# ETHERUNO.net
KiCad netlist of a schematic drawn in EAGLE
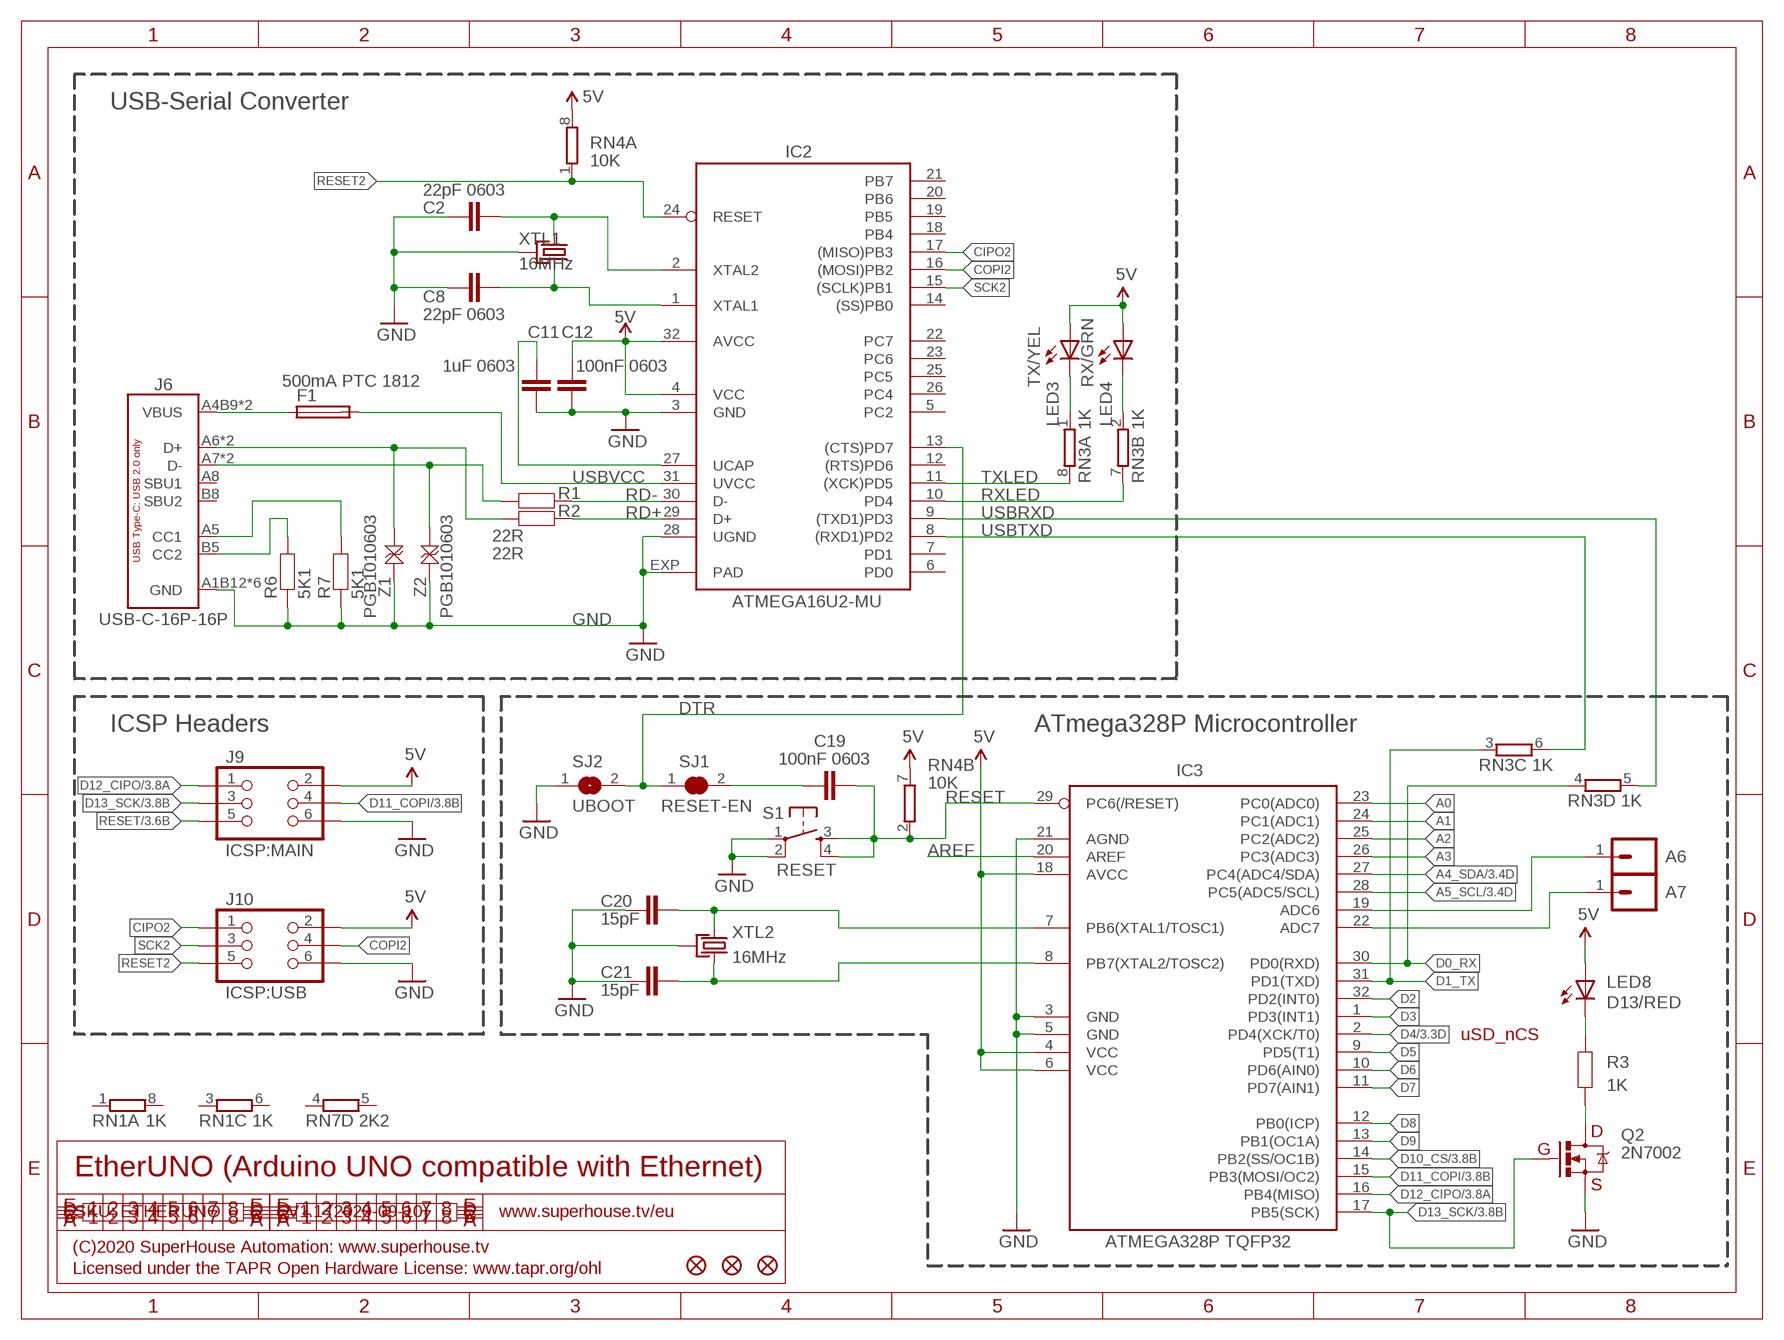
[diagram p0: schematic, sheet 1]
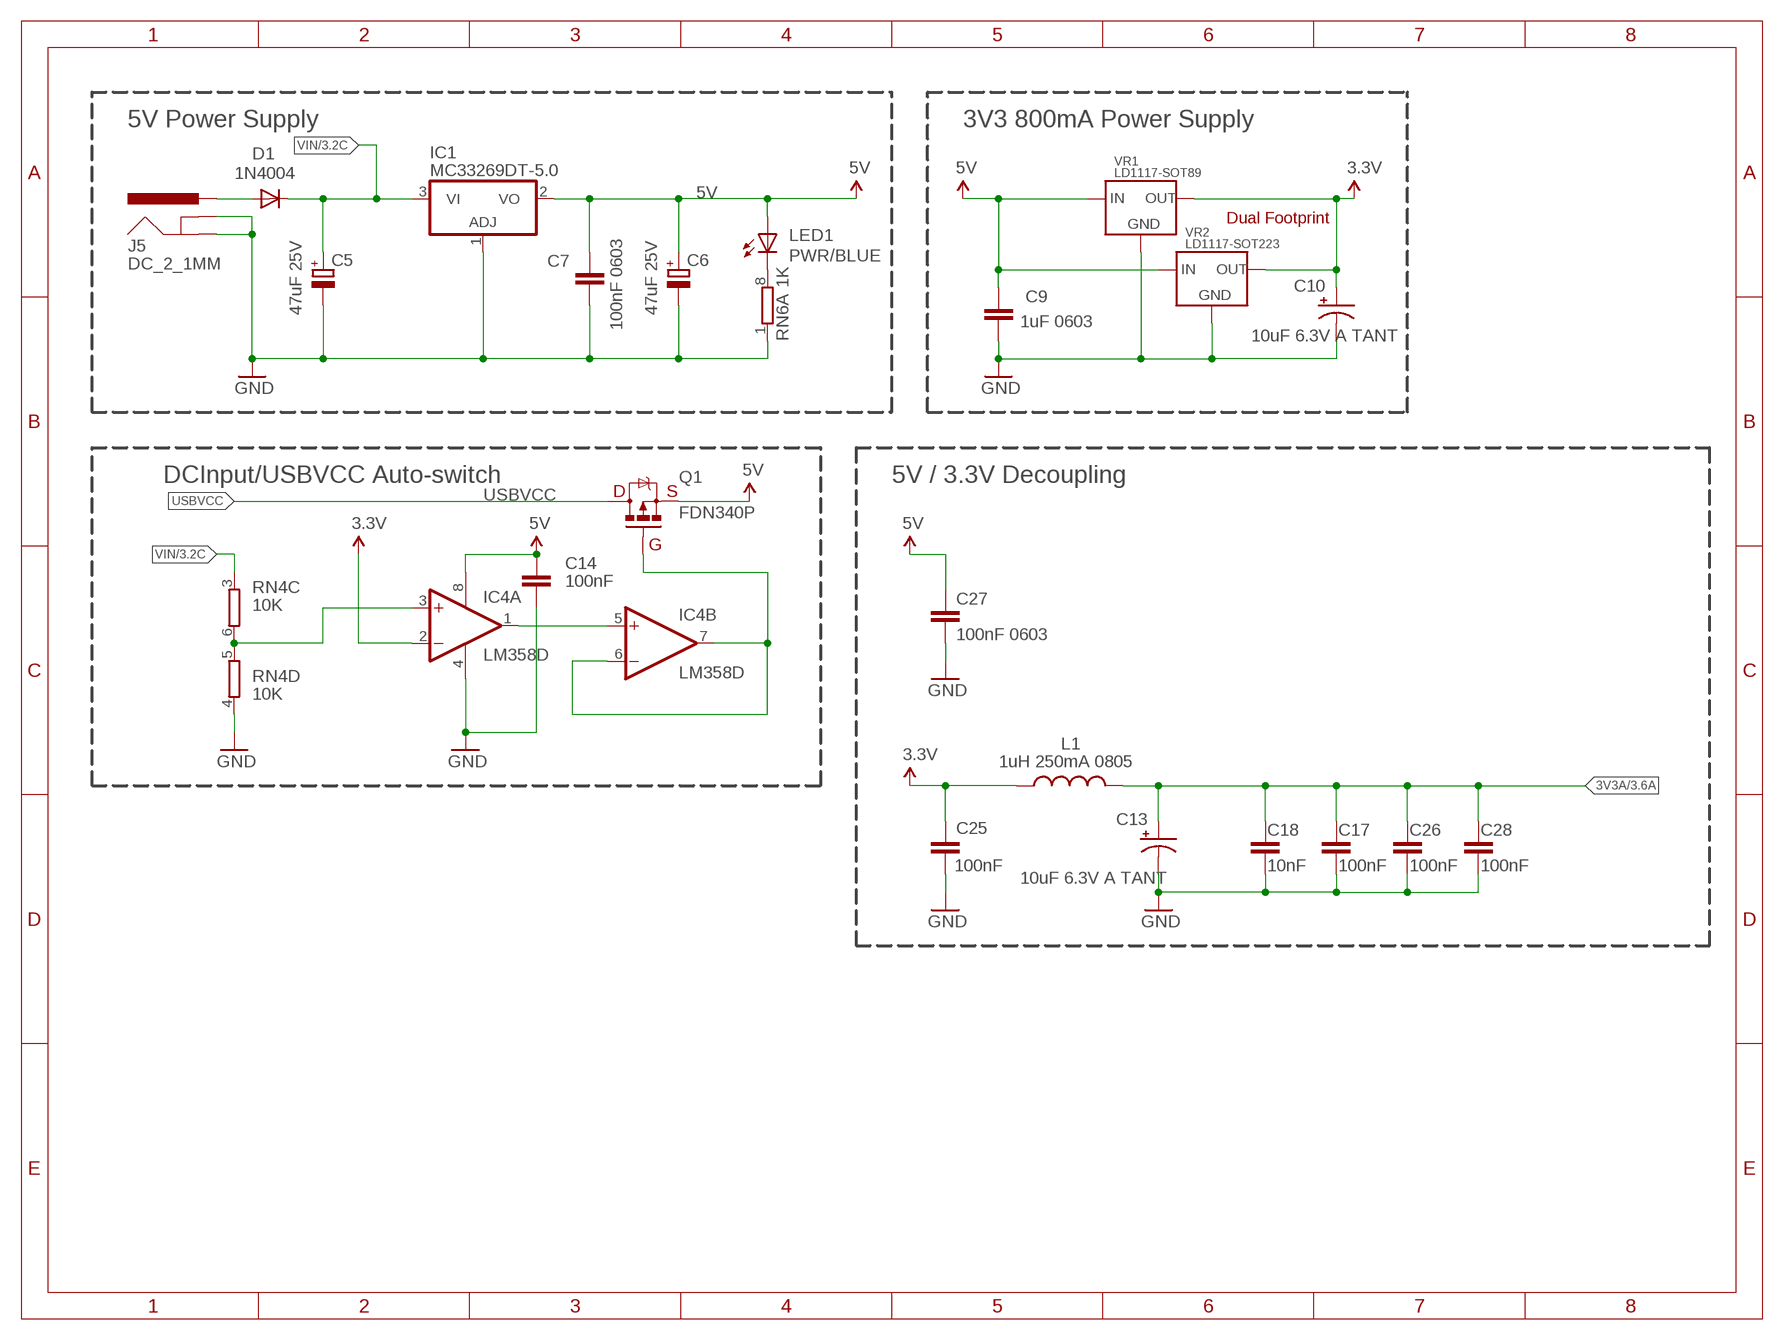
[diagram p1: schematic, sheet 2]
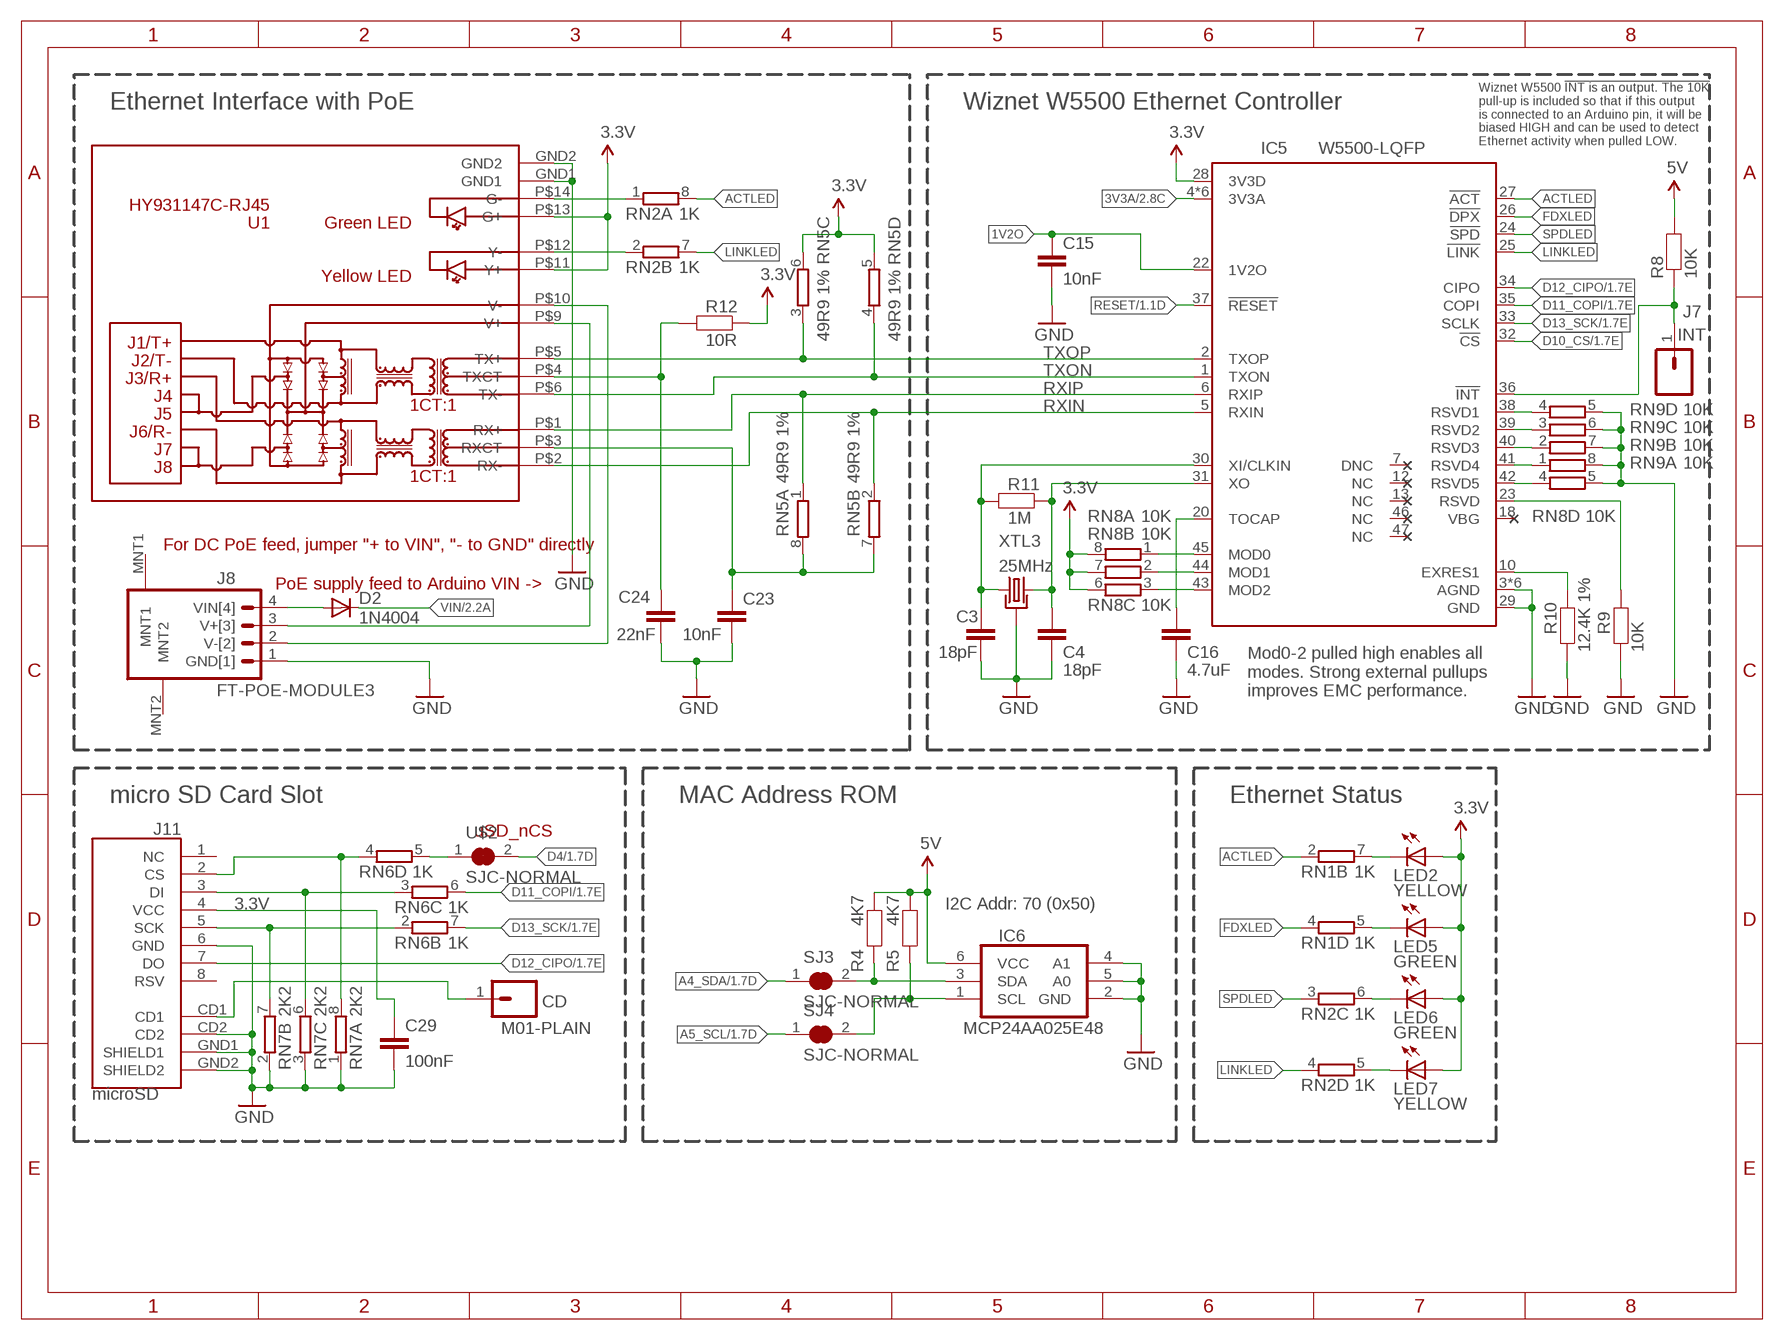
[diagram p2: schematic, sheet 3]
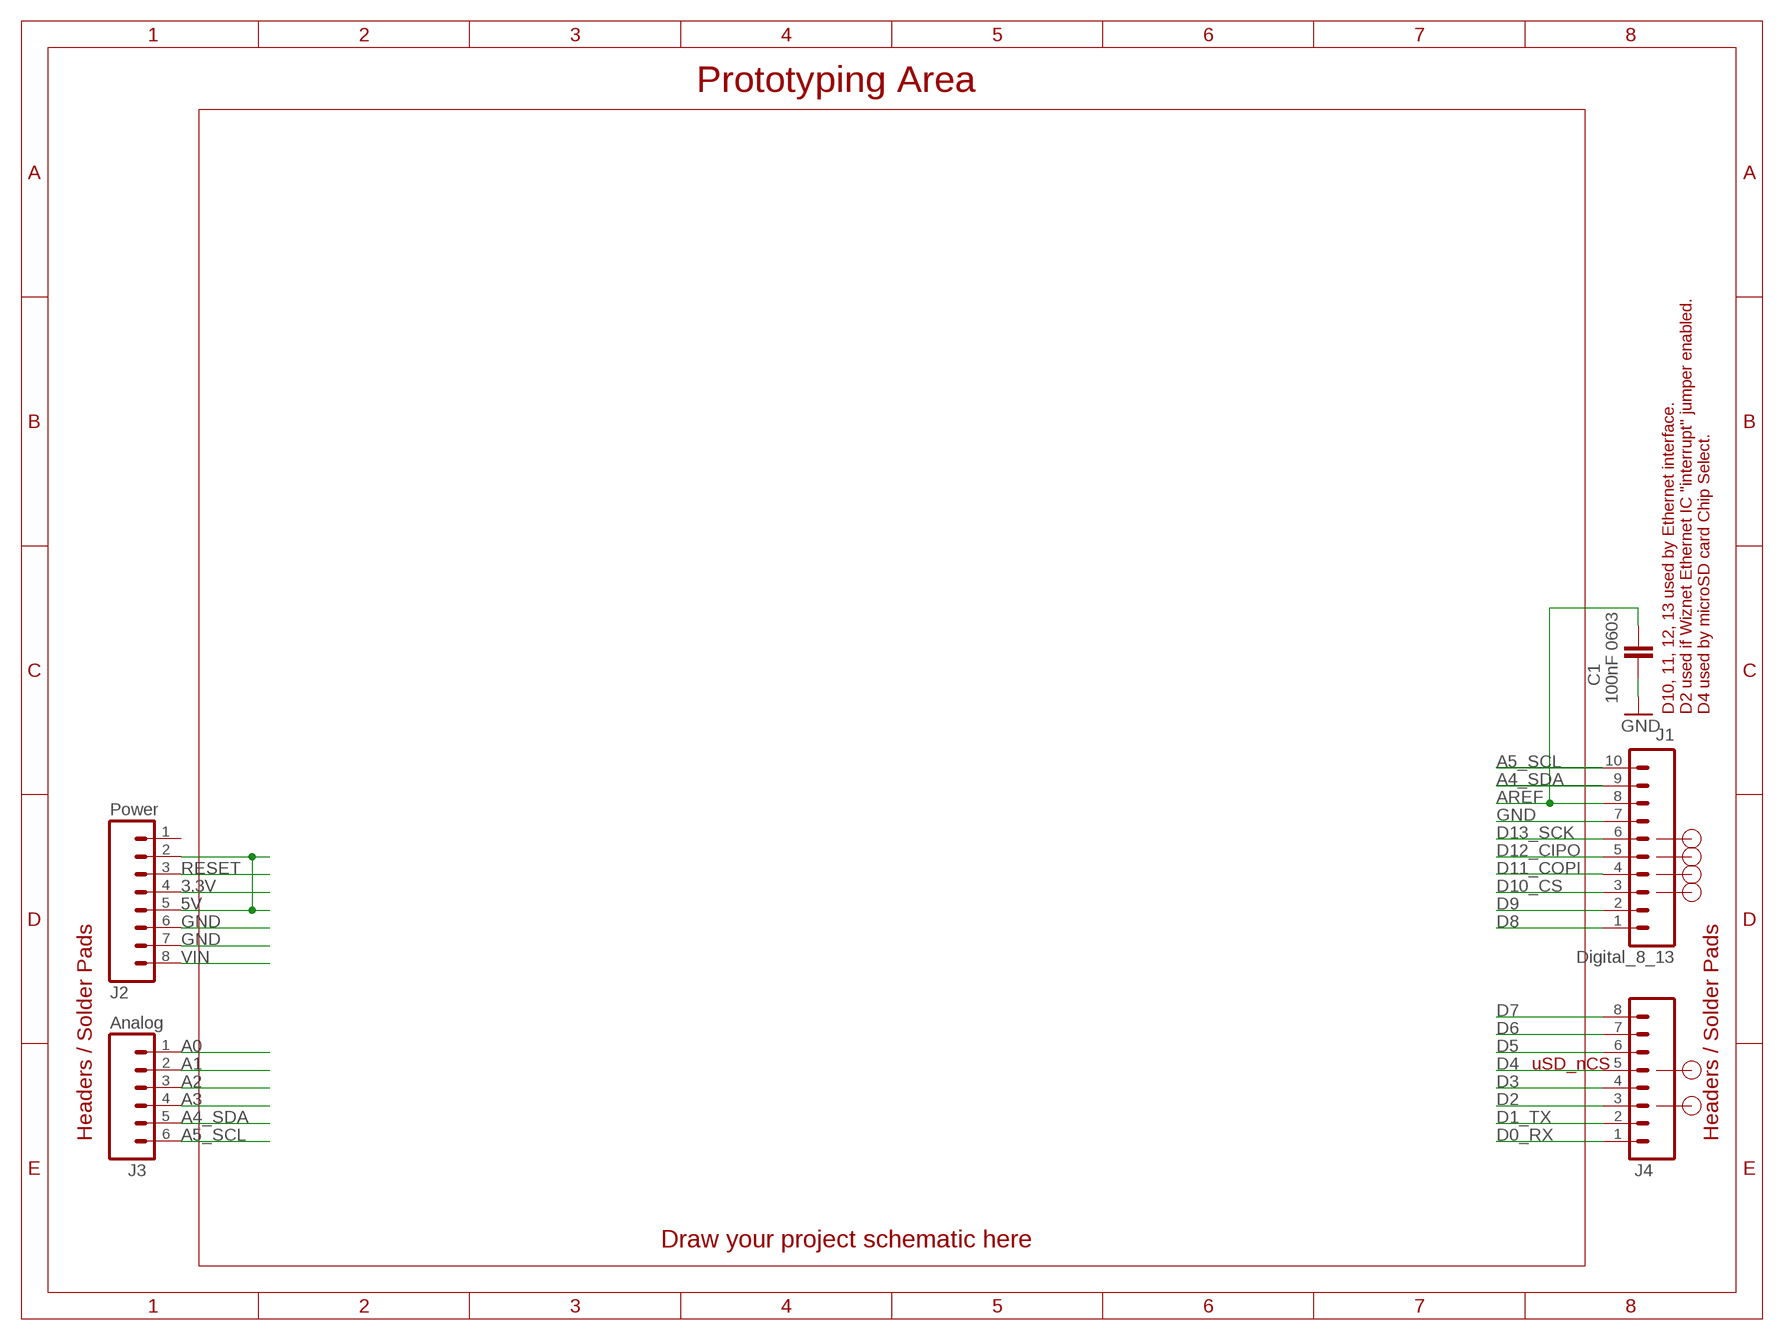
[diagram p3: schematic, sheet 4]

(export (version "E")
  (design (tool "Eeschema 10.0.6"))
  (components
    (comp (ref "A6")
      (value "A6")
      (footprint "eagle-import:1X01")
      (libsource (lib "eagle-import") (part "M01-PLAIN"))
    )
    (comp (ref "A7")
      (value "A7")
      (footprint "eagle-import:1X01")
      (libsource (lib "eagle-import") (part "M01-PLAIN"))
    )
    (comp (ref "C2")
      (value "22pF 0603")
      (footprint "eagle-import:C0603")
      (libsource (lib "eagle-import") (part "CAP0603"))
    )
    (comp (ref "C8")
      (value "22pF 0603")
      (footprint "eagle-import:C0603")
      (libsource (lib "eagle-import") (part "CAP0603"))
    )
    (comp (ref "C11")
      (value "1uF 0603")
      (footprint "eagle-import:C0603")
      (libsource (lib "eagle-import") (part "CAP0603"))
    )
    (comp (ref "C12")
      (value "100nF 0603")
      (footprint "eagle-import:C0603")
      (libsource (lib "eagle-import") (part "CAP0603"))
    )
    (comp (ref "C19")
      (value "100nF 0603")
      (footprint "eagle-import:C0603")
      (libsource (lib "eagle-import") (part "CAP0603"))
    )
    (comp (ref "C20")
      (value "15pF")
      (footprint "eagle-import:C0603")
      (libsource (lib "eagle-import") (part "CAP0603"))
    )
    (comp (ref "C21")
      (value "15pF")
      (footprint "eagle-import:C0603")
      (libsource (lib "eagle-import") (part "CAP0603"))
    )
    (comp (ref "F1")
      (value "500mA PTC 1812")
      (footprint "eagle-import:1812")
      (libsource (lib "eagle-import") (part "PTC050"))
    )
    (comp (ref "FID1")
      (value "FIDUCIAL1X2.5")
      (footprint "eagle-import:FIDUCIAL-1X2.5")
      (libsource (lib "eagle-import") (part "FIDUCIAL1X2.5"))
    )
    (comp (ref "FID2")
      (value "FIDUCIAL1X2.5")
      (footprint "eagle-import:FIDUCIAL-1X2.5")
      (libsource (lib "eagle-import") (part "FIDUCIAL1X2.5"))
    )
    (comp (ref "FID3")
      (value "FIDUCIAL1X2.5")
      (footprint "eagle-import:FIDUCIAL-1X2.5")
      (libsource (lib "eagle-import") (part "FIDUCIAL1X2.5"))
    )
    (comp (ref "IC2")
      (value "ATMEGA16U2-MU")
      (footprint "eagle-import:ATMEL_QFN32")
      (libsource (lib "eagle-import") (part "ATMEGA8U2QFN"))
    )
    (comp (ref "IC3")
      (value "ATMEGA328P TQFP32")
      (footprint "eagle-import:TQFP32-08")
      (libsource (lib "eagle-import") (part "AVR-MEGA8-AI"))
    )
    (comp (ref "J6")
      (value "USB-C-16P-16P")
      (footprint "eagle-import:USB-C-16P")
      (libsource (lib "eagle-import") (part "USB-C-16P-16P"))
    )
    (comp (ref "J9")
      (value "ICSP:MAIN")
      (footprint "eagle-import:2X03-ICSP")
      (libsource (lib "eagle-import") (part "ICSP-PIN"))
    )
    (comp (ref "J10")
      (value "ICSP:USB")
      (footprint "eagle-import:2X03-ICSP")
      (libsource (lib "eagle-import") (part "ICSP-PIN"))
    )
    (comp (ref "LED3")
      (value "TX/YEL")
      (footprint "eagle-import:LED-0603")
      (libsource (lib "eagle-import") (part "LED0603"))
    )
    (comp (ref "LED4")
      (value "RX/GRN")
      (footprint "eagle-import:LED-0603")
      (libsource (lib "eagle-import") (part "LED0603"))
    )
    (comp (ref "LED8")
      (value "D13/RED")
      (footprint "eagle-import:LED-0603")
      (libsource (lib "eagle-import") (part "LED0603"))
    )
    (comp (ref "Q2")
      (value "2N7002")
      (footprint "eagle-import:SOT23-3")
      (libsource (lib "eagle-import") (part "MOSFET-NCHANNEL-233"))
    )
    (comp (ref "R1")
      (value "22R")
      (footprint "eagle-import:R0603")
      (libsource (lib "eagle-import") (part "RESISTOR0603"))
    )
    (comp (ref "R2")
      (value "22R")
      (footprint "eagle-import:R0603")
      (libsource (lib "eagle-import") (part "RESISTOR0603"))
    )
    (comp (ref "R3")
      (value "1K")
      (footprint "eagle-import:R0603")
      (libsource (lib "eagle-import") (part "RESISTOR0603"))
    )
    (comp (ref "R6")
      (value "5K1")
      (footprint "eagle-import:R0603")
      (libsource (lib "eagle-import") (part "RESISTOR0603"))
    )
    (comp (ref "R7")
      (value "5K1")
      (footprint "eagle-import:R0603")
      (libsource (lib "eagle-import") (part "RESISTOR0603"))
    )
    (comp (ref "RN1")
      (value "1K")
      (footprint "eagle-import:CAY16")
      (libsource (lib "eagle-import") (part "4R-NCAY16"))
    )
    (comp (ref "RN3")
      (value "1K")
      (footprint "eagle-import:CAY16")
      (libsource (lib "eagle-import") (part "4R-NCAY16"))
    )
    (comp (ref "RN4")
      (value "10K")
      (footprint "eagle-import:CAY16")
      (libsource (lib "eagle-import") (part "4R-NCAY16"))
    )
    (comp (ref "RN7")
      (value "2K2")
      (footprint "eagle-import:CAY16")
      (libsource (lib "eagle-import") (part "4R-NCAY16"))
    )
    (comp (ref "S1")
      (value "RESET")
      (footprint "eagle-import:TACTILE_SMT-6MM")
      (libsource (lib "eagle-import") (part "TAC_SWITCH-SMT-6"))
    )
    (comp (ref "SJ1")
      (value "RESET-EN")
      (footprint "eagle-import:SJC")
      (libsource (lib "eagle-import") (part "SJC-NORMAL"))
    )
    (comp (ref "SJ2")
      (value "UBOOT")
      (footprint "eagle-import:SJ")
      (libsource (lib "eagle-import") (part "SJ-NORMAL"))
    )
    (comp (ref "XTL1")
      (value "16MHz")
      (footprint "eagle-import:CRYSTAL-SMD-3X2")
      (libsource (lib "eagle-import") (part "CRYSTAL-GND3X2"))
    )
    (comp (ref "XTL2")
      (value "16MHz")
      (footprint "eagle-import:CRYSTAL-SMD-3X2")
      (libsource (lib "eagle-import") (part "CRYSTAL-GND3X2"))
    )
    (comp (ref "Z1")
      (value "PGB1010603")
      (footprint "eagle-import:TVS0603")
      (libsource (lib "eagle-import") (part "TVS0603"))
    )
    (comp (ref "Z2")
      (value "PGB1010603")
      (footprint "eagle-import:TVS0603")
      (libsource (lib "eagle-import") (part "TVS0603"))
    )
    (comp (ref "C1")
      (value "100nF 0603")
      (footprint "eagle-import:C0603")
      (libsource (lib "eagle-import") (part "CAP0603"))
    )
    (comp (ref "J1")
      (value "Digital_8_13")
      (footprint "eagle-import:1X10-S")
      (libsource (lib "eagle-import") (part "M10-SOCKET"))
    )
    (comp (ref "J2")
      (value "Power")
      (footprint "eagle-import:1X08-S")
      (libsource (lib "eagle-import") (part "M08-SOCKET"))
    )
    (comp (ref "J3")
      (value "Analog")
      (footprint "eagle-import:1X06-S")
      (libsource (lib "eagle-import") (part "M06-SOCKET"))
    )
    (comp (ref "J4")
      (value "Digital_0_7")
      (footprint "eagle-import:1X08-S")
      (libsource (lib "eagle-import") (part "M08-SOCKET"))
    )
    (comp (ref "C3")
      (value "18pF")
      (footprint "eagle-import:C0603")
      (libsource (lib "eagle-import") (part "CAP0603"))
    )
    (comp (ref "C4")
      (value "18pF")
      (footprint "eagle-import:C0603")
      (libsource (lib "eagle-import") (part "CAP0603"))
    )
    (comp (ref "C15")
      (value "10nF")
      (footprint "eagle-import:C0603")
      (libsource (lib "eagle-import") (part "CAP0603"))
    )
    (comp (ref "C16")
      (value "4.7uF")
      (footprint "eagle-import:C0603")
      (libsource (lib "eagle-import") (part "CAP0603"))
    )
    (comp (ref "C23")
      (value "10nF")
      (footprint "eagle-import:C0603")
      (libsource (lib "eagle-import") (part "CAP0603"))
    )
    (comp (ref "C24")
      (value "22nF")
      (footprint "eagle-import:C0603")
      (libsource (lib "eagle-import") (part "CAP0603"))
    )
    (comp (ref "C29")
      (value "100nF")
      (footprint "eagle-import:C0603")
      (libsource (lib "eagle-import") (part "CAP0603"))
    )
    (comp (ref "CD")
      (value "M01-PLAIN")
      (footprint "eagle-import:1X01")
      (libsource (lib "eagle-import") (part "M01-PLAIN"))
    )
    (comp (ref "D2")
      (value "1N4004")
      (footprint "eagle-import:SMA-DIODE")
      (libsource (lib "eagle-import") (part "DIODESMA"))
    )
    (comp (ref "IC5")
      (value "W5500-LQFP")
      (footprint "eagle-import:LQFP48")
      (libsource (lib "eagle-import") (part "W5500-LQFP"))
    )
    (comp (ref "IC6")
      (value "MCP24AA025E48")
      (footprint "eagle-import:SOT23-6")
      (libsource (lib "eagle-import") (part "MCP24AA025E48"))
    )
    (comp (ref "J7")
      (value "INT")
      (footprint "eagle-import:1X01")
      (libsource (lib "eagle-import") (part "M01-PLAIN"))
    )
    (comp (ref "J8")
      (value "FT-POE-MODULE3")
      (footprint "eagle-import:FT-POE-MODULE-NOLABEL")
      (libsource (lib "eagle-import") (part "FT-POE-MODULE3"))
    )
    (comp (ref "J11")
      (value "microSD")
      (footprint "eagle-import:MICRO-SD-SOCKET-PP")
      (libsource (lib "eagle-import") (part "USD-SOCKETNEW"))
    )
    (comp (ref "LED2")
      (value "YELLOW")
      (footprint "eagle-import:LED-0603")
      (libsource (lib "eagle-import") (part "LED0603"))
    )
    (comp (ref "LED5")
      (value "GREEN")
      (footprint "eagle-import:LED-0603")
      (libsource (lib "eagle-import") (part "LED0603"))
    )
    (comp (ref "LED6")
      (value "GREEN")
      (footprint "eagle-import:LED-0603")
      (libsource (lib "eagle-import") (part "LED0603"))
    )
    (comp (ref "LED7")
      (value "YELLOW")
      (footprint "eagle-import:LED-0603")
      (libsource (lib "eagle-import") (part "LED0603"))
    )
    (comp (ref "R4")
      (value "4K7")
      (footprint "eagle-import:R0603")
      (libsource (lib "eagle-import") (part "RESISTOR0603"))
    )
    (comp (ref "R5")
      (value "4K7")
      (footprint "eagle-import:R0603")
      (libsource (lib "eagle-import") (part "RESISTOR0603"))
    )
    (comp (ref "R8")
      (value "10K")
      (footprint "eagle-import:R0603")
      (libsource (lib "eagle-import") (part "RESISTOR0603"))
    )
    (comp (ref "R9")
      (value "10K")
      (footprint "eagle-import:R0603")
      (libsource (lib "eagle-import") (part "RESISTOR0603"))
    )
    (comp (ref "R10")
      (value "12.4K 1%")
      (footprint "eagle-import:R0603")
      (libsource (lib "eagle-import") (part "RESISTOR0603"))
    )
    (comp (ref "R11")
      (value "1M")
      (footprint "eagle-import:R0603")
      (libsource (lib "eagle-import") (part "RESISTOR0603"))
    )
    (comp (ref "R12")
      (value "10R")
      (footprint "eagle-import:R0603")
      (libsource (lib "eagle-import") (part "RESISTOR0603"))
    )
    (comp (ref "RN2")
      (value "1K")
      (footprint "eagle-import:CAY16")
      (libsource (lib "eagle-import") (part "4R-NCAY16"))
    )
    (comp (ref "RN5")
      (value "49R9 1%")
      (footprint "eagle-import:CAY16")
      (libsource (lib "eagle-import") (part "4R-NCAY16"))
    )
    (comp (ref "RN6")
      (value "1K")
      (footprint "eagle-import:CAY16")
      (libsource (lib "eagle-import") (part "4R-NCAY16"))
    )
    (comp (ref "RN8")
      (value "10K")
      (footprint "eagle-import:CAY16")
      (libsource (lib "eagle-import") (part "4R-NCAY16"))
    )
    (comp (ref "RN9")
      (value "10K")
      (footprint "eagle-import:CAY16")
      (libsource (lib "eagle-import") (part "4R-NCAY16"))
    )
    (comp (ref "SJ3")
      (value "SJC-NORMAL")
      (footprint "eagle-import:SJC")
      (libsource (lib "eagle-import") (part "SJC-NORMAL"))
    )
    (comp (ref "SJ4")
      (value "SJC-NORMAL")
      (footprint "eagle-import:SJC")
      (libsource (lib "eagle-import") (part "SJC-NORMAL"))
    )
    (comp (ref "U$2")
      (value "SJC-NORMAL")
      (footprint "eagle-import:SJC")
      (libsource (lib "eagle-import") (part "SJC-NORMAL"))
    )
    (comp (ref "U1")
      (value "HY931147C-RJ45")
      (footprint "eagle-import:HY931147C")
      (libsource (lib "eagle-import") (part "HY931147C-RJ45"))
    )
    (comp (ref "XTL3")
      (value "25MHz")
      (footprint "eagle-import:CRYSTAL-SMD-3X2")
      (libsource (lib "eagle-import") (part "CRYSTAL-GND3X2"))
    )
    (comp (ref "C5")
      (value "47uF 25V")
      (footprint "eagle-import:PANASONIC_D")
      (libsource (lib "eagle-import") (part "CPOL-EUD"))
    )
    (comp (ref "C6")
      (value "47uF 25V")
      (footprint "eagle-import:PANASONIC_D")
      (libsource (lib "eagle-import") (part "CPOL-EUD"))
    )
    (comp (ref "C7")
      (value "100nF 0603")
      (footprint "eagle-import:C0603")
      (libsource (lib "eagle-import") (part "CAP0603"))
    )
    (comp (ref "C9")
      (value "1uF 0603")
      (footprint "eagle-import:C0603")
      (libsource (lib "eagle-import") (part "CAP0603"))
    )
    (comp (ref "C10")
      (value "10uF 6.3V A TANT")
      (footprint "eagle-import:EIA3216")
      (libsource (lib "eagle-import") (part "CAP_POL1206"))
    )
    (comp (ref "C13")
      (value "10uF 6.3V A TANT")
      (footprint "eagle-import:EIA3216")
      (libsource (lib "eagle-import") (part "CAP_POL1206"))
    )
    (comp (ref "C14")
      (value "100nF")
      (footprint "eagle-import:C0603")
      (libsource (lib "eagle-import") (part "CAP0603"))
    )
    (comp (ref "C17")
      (value "100nF")
      (footprint "eagle-import:C0603")
      (libsource (lib "eagle-import") (part "CAP0603"))
    )
    (comp (ref "C18")
      (value "10nF")
      (footprint "eagle-import:C0603")
      (libsource (lib "eagle-import") (part "CAP0603"))
    )
    (comp (ref "C25")
      (value "100nF")
      (footprint "eagle-import:C0603")
      (libsource (lib "eagle-import") (part "CAP0603"))
    )
    (comp (ref "C26")
      (value "100nF")
      (footprint "eagle-import:C0603")
      (libsource (lib "eagle-import") (part "CAP0603"))
    )
    (comp (ref "C27")
      (value "100nF 0603")
      (footprint "eagle-import:C0603")
      (libsource (lib "eagle-import") (part "CAP0603"))
    )
    (comp (ref "C28")
      (value "100nF")
      (footprint "eagle-import:C0603")
      (libsource (lib "eagle-import") (part "CAP0603"))
    )
    (comp (ref "D1")
      (value "1N4004")
      (footprint "eagle-import:SMA-DIODE")
      (libsource (lib "eagle-import") (part "DIODESMA"))
    )
    (comp (ref "IC1")
      (value "MC33269DT-5.0")
      (footprint "eagle-import:DPACK")
      (libsource (lib "eagle-import") (part "MC33269-X-D-5.0"))
    )
    (comp (ref "IC4")
      (value "LM358D")
      (footprint "eagle-import:SO08")
      (libsource (lib "eagle-import") (part "LM358D"))
    )
    (comp (ref "J5")
      (value "DC_2_1MM")
      (footprint "eagle-import:POWER_JACK_SLOTS")
      (libsource (lib "eagle-import") (part "POWER_JACK-SLOTS"))
    )
    (comp (ref "L1")
      (value "1uH 250mA 0805")
      (footprint "eagle-import:L2012C")
      (libsource (lib "eagle-import") (part "L-USL2012C"))
    )
    (comp (ref "LED1")
      (value "PWR/BLUE")
      (footprint "eagle-import:LED-0603")
      (libsource (lib "eagle-import") (part "LED0603"))
    )
    (comp (ref "Q1")
      (value "FDN340P")
      (footprint "eagle-import:SOT23")
      (libsource (lib "eagle-import") (part "MOSFET-PCHANNEL"))
    )
    (comp (ref "VR1")
      (value "LD1117-SOT89")
      (footprint "eagle-import:SOT89")
      (libsource (lib "eagle-import") (part "LD1117-SOT89"))
    )
    (comp (ref "VR2")
      (value "LD1117-SOT223")
      (footprint "eagle-import:SOT-223")
      (libsource (lib "eagle-import") (part "LD1117-SOT223"))
    )
  )
  (nets
    (net (code "1") (name "1V2O") (class "Default")
      (node (ref "C15") (pin "1") (pinfunction "1_1") (pintype "passive"))
      (node (ref "IC5") (pin "22") (pinfunction "1V2O_22") (pintype "passive"))
    )
    (net (code "2") (name "3.3V") (class "Default")
      (node (ref "C10") (pin "A") (pinfunction "+_A") (pintype "passive"))
      (node (ref "C25") (pin "1") (pinfunction "1_1") (pintype "passive"))
      (node (ref "C29") (pin "1") (pinfunction "1_1") (pintype "passive"))
      (node (ref "IC4") (pin "2") (pinfunction "-IN_2") (pintype "input"))
      (node (ref "IC5") (pin "28") (pinfunction "3V3D_28") (pintype "passive"))
      (node (ref "J11") (pin "4") (pinfunction "VCC_4") (pintype "bidirectional"))
      (node (ref "J2") (pin "4") (pinfunction "4_4") (pintype "passive"))
      (node (ref "L1") (pin "1") (pinfunction "1_1") (pintype "passive"))
      (node (ref "LED2") (pin "A") (pinfunction "A_A") (pintype "passive"))
      (node (ref "LED5") (pin "A") (pinfunction "A_A") (pintype "passive"))
      (node (ref "LED6") (pin "A") (pinfunction "A_A") (pintype "passive"))
      (node (ref "LED7") (pin "A") (pinfunction "A_A") (pintype "passive"))
      (node (ref "R12") (pin "1") (pinfunction "1_1") (pintype "passive"))
      (node (ref "RN5") (pin "5") (pinfunction "2_5") (pintype "passive"))
      (node (ref "RN5") (pin "6") (pinfunction "2_6") (pintype "passive"))
      (node (ref "RN8") (pin "6") (pinfunction "2_6") (pintype "passive"))
      (node (ref "RN8") (pin "7") (pinfunction "2_7") (pintype "passive"))
      (node (ref "RN8") (pin "8") (pinfunction "2_8") (pintype "passive"))
      (node (ref "U1") (pin "P$11") (pinfunction "Y+_P$11") (pintype "bidirectional"))
      (node (ref "U1") (pin "P$13") (pinfunction "G+_P$13") (pintype "bidirectional"))
      (node (ref "VR1") (pin "2") (pinfunction "OUT_2") (pintype "power_in"))
      (node (ref "VR1") (pin "4") (pinfunction "OUT_4") (pintype "power_in"))
      (node (ref "VR2") (pin "2") (pinfunction "OUT_2") (pintype "power_in"))
      (node (ref "VR2") (pin "4") (pinfunction "OUT_4") (pintype "power_in"))
    )
    (net (code "3") (name "3V3A") (class "Default")
      (node (ref "C13") (pin "A") (pinfunction "+_A") (pintype "passive"))
      (node (ref "C17") (pin "1") (pinfunction "1_1") (pintype "passive"))
      (node (ref "C18") (pin "1") (pinfunction "1_1") (pintype "passive"))
      (node (ref "C26") (pin "1") (pinfunction "1_1") (pintype "passive"))
      (node (ref "C28") (pin "1") (pinfunction "1_1") (pintype "passive"))
      (node (ref "IC5") (pin "11") (pinfunction "3V3A_11") (pintype "passive"))
      (node (ref "IC5") (pin "15") (pinfunction "3V3A_15") (pintype "passive"))
      (node (ref "IC5") (pin "17") (pinfunction "3V3A_17") (pintype "passive"))
      (node (ref "IC5") (pin "21") (pinfunction "3V3A_21") (pintype "passive"))
      (node (ref "IC5") (pin "4") (pinfunction "3V3A_4") (pintype "passive"))
      (node (ref "IC5") (pin "8") (pinfunction "3V3A_8") (pintype "passive"))
      (node (ref "L1") (pin "2") (pinfunction "2_2") (pintype "passive"))
    )
    (net (code "4") (name "5V") (class "Default")
      (node (ref "C12") (pin "1") (pinfunction "1_1") (pintype "passive"))
      (node (ref "C14") (pin "1") (pinfunction "1_1") (pintype "passive"))
      (node (ref "C27") (pin "1") (pinfunction "1_1") (pintype "passive"))
      (node (ref "C6") (pin "+") (pinfunction "+_+") (pintype "passive"))
      (node (ref "C7") (pin "1") (pinfunction "1_1") (pintype "passive"))
      (node (ref "C9") (pin "1") (pinfunction "1_1") (pintype "passive"))
      (node (ref "IC1") (pin "2") (pinfunction "VO_2") (pintype "passive"))
      (node (ref "IC2") (pin "32") (pinfunction "AVCC_32") (pintype "power_in"))
      (node (ref "IC2") (pin "4") (pinfunction "VCC_4") (pintype "power_in"))
      (node (ref "IC3") (pin "18") (pinfunction "AVCC_18") (pintype "bidirectional"))
      (node (ref "IC3") (pin "4") (pinfunction "VCC_4") (pintype "bidirectional"))
      (node (ref "IC3") (pin "6") (pinfunction "VCC_6") (pintype "bidirectional"))
      (node (ref "IC4") (pin "8") (pinfunction "V+_8") (pintype "power_in"))
      (node (ref "IC6") (pin "6") (pinfunction "VCC_6") (pintype "power_in"))
      (node (ref "J10") (pin "2") (pinfunction "2_2") (pintype "passive"))
      (node (ref "J2") (pin "2") (pinfunction "2_2") (pintype "passive"))
      (node (ref "J2") (pin "5") (pinfunction "5_5") (pintype "passive"))
      (node (ref "J9") (pin "2") (pinfunction "2_2") (pintype "passive"))
      (node (ref "LED1") (pin "A") (pinfunction "A_A") (pintype "passive"))
      (node (ref "LED3") (pin "A") (pinfunction "A_A") (pintype "passive"))
      (node (ref "LED4") (pin "A") (pinfunction "A_A") (pintype "passive"))
      (node (ref "LED8") (pin "A") (pinfunction "A_A") (pintype "passive"))
      (node (ref "Q1") (pin "2") (pinfunction "S_2") (pintype "passive"))
      (node (ref "R4") (pin "1") (pinfunction "1_1") (pintype "passive"))
      (node (ref "R5") (pin "1") (pinfunction "1_1") (pintype "passive"))
      (node (ref "R8") (pin "2") (pinfunction "2_2") (pintype "passive"))
      (node (ref "RN4") (pin "7") (pinfunction "2_7") (pintype "passive"))
      (node (ref "RN4") (pin "8") (pinfunction "2_8") (pintype "passive"))
      (node (ref "VR1") (pin "3") (pinfunction "IN_3") (pintype "input"))
      (node (ref "VR2") (pin "3") (pinfunction "IN_3") (pintype "input"))
    )
    (net (code "5") (name "A0") (class "Default")
      (node (ref "IC3") (pin "23") (pinfunction "PC0(ADC0)_23") (pintype "bidirectional"))
      (node (ref "J3") (pin "1") (pinfunction "1_1") (pintype "passive"))
    )
    (net (code "6") (name "A1") (class "Default")
      (node (ref "IC3") (pin "24") (pinfunction "PC1(ADC1)_24") (pintype "bidirectional"))
      (node (ref "J3") (pin "2") (pinfunction "2_2") (pintype "passive"))
    )
    (net (code "7") (name "A2") (class "Default")
      (node (ref "IC3") (pin "25") (pinfunction "PC2(ADC2)_25") (pintype "bidirectional"))
      (node (ref "J3") (pin "3") (pinfunction "3_3") (pintype "passive"))
    )
    (net (code "8") (name "A3") (class "Default")
      (node (ref "IC3") (pin "26") (pinfunction "PC3(ADC3)_26") (pintype "bidirectional"))
      (node (ref "J3") (pin "4") (pinfunction "4_4") (pintype "passive"))
    )
    (net (code "9") (name "A4_SDA") (class "Default")
      (node (ref "IC3") (pin "27") (pinfunction "PC4(ADC4/SDA)_27") (pintype "bidirectional"))
      (node (ref "J1") (pin "9") (pinfunction "9_9") (pintype "passive"))
      (node (ref "J3") (pin "5") (pinfunction "5_5") (pintype "passive"))
      (node (ref "SJ3") (pin "1") (pinfunction "1_1") (pintype "passive"))
    )
    (net (code "10") (name "A5_SCL") (class "Default")
      (node (ref "IC3") (pin "28") (pinfunction "PC5(ADC5/SCL)_28") (pintype "bidirectional"))
      (node (ref "J1") (pin "10") (pinfunction "10_10") (pintype "passive"))
      (node (ref "J3") (pin "6") (pinfunction "6_6") (pintype "passive"))
      (node (ref "SJ4") (pin "1") (pinfunction "1_1") (pintype "passive"))
    )
    (net (code "11") (name "ACTLED") (class "Default")
      (node (ref "IC5") (pin "27") (pinfunction "~{ACT}_27") (pintype "passive"))
      (node (ref "RN1") (pin "2") (pinfunction "1_2") (pintype "passive"))
      (node (ref "RN2") (pin "8") (pinfunction "2_8") (pintype "passive"))
    )
    (net (code "12") (name "AREF") (class "Default")
      (node (ref "C1") (pin "1") (pinfunction "1_1") (pintype "passive"))
      (node (ref "IC3") (pin "20") (pinfunction "AREF_20") (pintype "bidirectional"))
      (node (ref "J1") (pin "8") (pinfunction "8_8") (pintype "passive"))
    )
    (net (code "13") (name "CIPO2") (class "Default")
      (node (ref "IC2") (pin "17") (pinfunction "(MISO)PB3_17") (pintype "bidirectional"))
      (node (ref "J10") (pin "1") (pinfunction "1_1") (pintype "passive"))
    )
    (net (code "14") (name "COPI2") (class "Default")
      (node (ref "IC2") (pin "16") (pinfunction "(MOSI)PB2_16") (pintype "bidirectional"))
      (node (ref "J10") (pin "4") (pinfunction "4_4") (pintype "passive"))
    )
    (net (code "15") (name "D0_RX") (class "Default")
      (node (ref "IC3") (pin "30") (pinfunction "PD0(RXD)_30") (pintype "bidirectional"))
      (node (ref "J4") (pin "1") (pinfunction "1_1") (pintype "passive"))
      (node (ref "RN3") (pin "4") (pinfunction "1_4") (pintype "passive"))
    )
    (net (code "16") (name "D1_TX") (class "Default")
      (node (ref "IC3") (pin "31") (pinfunction "PD1(TXD)_31") (pintype "bidirectional"))
      (node (ref "J4") (pin "2") (pinfunction "2_2") (pintype "passive"))
      (node (ref "RN3") (pin "3") (pinfunction "1_3") (pintype "passive"))
    )
    (net (code "17") (name "D2") (class "Default")
      (node (ref "IC3") (pin "32") (pinfunction "PD2(INT0)_32") (pintype "bidirectional"))
      (node (ref "J4") (pin "3") (pinfunction "3_3") (pintype "passive"))
    )
    (net (code "18") (name "D3") (class "Default")
      (node (ref "IC3") (pin "1") (pinfunction "PD3(INT1)_1") (pintype "bidirectional"))
      (node (ref "J4") (pin "4") (pinfunction "4_4") (pintype "passive"))
    )
    (net (code "19") (name "D4") (class "Default")
      (node (ref "IC3") (pin "2") (pinfunction "PD4(XCK/T0)_2") (pintype "bidirectional"))
      (node (ref "J4") (pin "5") (pinfunction "5_5") (pintype "passive"))
      (node (ref "U$2") (pin "2") (pinfunction "2_2") (pintype "passive"))
    )
    (net (code "20") (name "D5") (class "Default")
      (node (ref "IC3") (pin "9") (pinfunction "PD5(T1)_9") (pintype "bidirectional"))
      (node (ref "J4") (pin "6") (pinfunction "6_6") (pintype "passive"))
    )
    (net (code "21") (name "D6") (class "Default")
      (node (ref "IC3") (pin "10") (pinfunction "PD6(AIN0)_10") (pintype "bidirectional"))
      (node (ref "J4") (pin "7") (pinfunction "7_7") (pintype "passive"))
    )
    (net (code "22") (name "D7") (class "Default")
      (node (ref "IC3") (pin "11") (pinfunction "PD7(AIN1)_11") (pintype "bidirectional"))
      (node (ref "J4") (pin "8") (pinfunction "8_8") (pintype "passive"))
    )
    (net (code "23") (name "D8") (class "Default")
      (node (ref "IC3") (pin "12") (pinfunction "PB0(ICP)_12") (pintype "bidirectional"))
      (node (ref "J1") (pin "1") (pinfunction "1_1") (pintype "passive"))
    )
    (net (code "24") (name "D9") (class "Default")
      (node (ref "IC3") (pin "13") (pinfunction "PB1(OC1A)_13") (pintype "bidirectional"))
      (node (ref "J1") (pin "2") (pinfunction "2_2") (pintype "passive"))
    )
    (net (code "25") (name "D10_CS") (class "Default")
      (node (ref "IC3") (pin "14") (pinfunction "PB2(SS/OC1B)_14") (pintype "bidirectional"))
      (node (ref "IC5") (pin "32") (pinfunction "~{CS}_32") (pintype "passive"))
      (node (ref "J1") (pin "3") (pinfunction "3_3") (pintype "passive"))
    )
    (net (code "26") (name "D11_COPI") (class "Default")
      (node (ref "IC3") (pin "15") (pinfunction "PB3(MOSI/OC2)_15") (pintype "bidirectional"))
      (node (ref "IC5") (pin "35") (pinfunction "COPI_35") (pintype "passive"))
      (node (ref "J1") (pin "4") (pinfunction "4_4") (pintype "passive"))
      (node (ref "J9") (pin "4") (pinfunction "4_4") (pintype "passive"))
      (node (ref "RN6") (pin "6") (pinfunction "2_6") (pintype "passive"))
    )
    (net (code "27") (name "D12_CIPO") (class "Default")
      (node (ref "IC3") (pin "16") (pinfunction "PB4(MISO)_16") (pintype "bidirectional"))
      (node (ref "IC5") (pin "34") (pinfunction "CIPO_34") (pintype "passive"))
      (node (ref "J1") (pin "5") (pinfunction "5_5") (pintype "passive"))
      (node (ref "J11") (pin "7") (pinfunction "DO_7") (pintype "bidirectional"))
      (node (ref "J9") (pin "1") (pinfunction "1_1") (pintype "passive"))
    )
    (net (code "28") (name "D13_SCK") (class "Default")
      (node (ref "IC3") (pin "17") (pinfunction "PB5(SCK)_17") (pintype "bidirectional"))
      (node (ref "IC5") (pin "33") (pinfunction "SCLK_33") (pintype "passive"))
      (node (ref "J1") (pin "6") (pinfunction "6_6") (pintype "passive"))
      (node (ref "J9") (pin "3") (pinfunction "3_3") (pintype "passive"))
      (node (ref "Q2") (pin "1") (pinfunction "G_1") (pintype "passive"))
      (node (ref "RN6") (pin "7") (pinfunction "2_7") (pintype "passive"))
    )
    (net (code "29") (name "DTR") (class "Default")
      (node (ref "IC2") (pin "13") (pinfunction "(CTS)PD7_13") (pintype "bidirectional"))
      (node (ref "SJ1") (pin "1") (pinfunction "1_1") (pintype "passive"))
      (node (ref "SJ2") (pin "2") (pinfunction "2_2") (pintype "passive"))
    )
    (net (code "30") (name "FDXLED") (class "Default")
      (node (ref "IC5") (pin "26") (pinfunction "~{DPX}_26") (pintype "passive"))
      (node (ref "RN1") (pin "4") (pinfunction "1_4") (pintype "passive"))
    )
    (net (code "31") (name "GND") (class "Default")
      (node (ref "C1") (pin "2") (pinfunction "2_2") (pintype "passive"))
      (node (ref "C10") (pin "C") (pinfunction "-_C") (pintype "passive"))
      (node (ref "C11") (pin "2") (pinfunction "2_2") (pintype "passive"))
      (node (ref "C12") (pin "2") (pinfunction "2_2") (pintype "passive"))
      (node (ref "C13") (pin "C") (pinfunction "-_C") (pintype "passive"))
      (node (ref "C14") (pin "2") (pinfunction "2_2") (pintype "passive"))
      (node (ref "C15") (pin "2") (pinfunction "2_2") (pintype "passive"))
      (node (ref "C16") (pin "2") (pinfunction "2_2") (pintype "passive"))
      (node (ref "C17") (pin "2") (pinfunction "2_2") (pintype "passive"))
      (node (ref "C18") (pin "2") (pinfunction "2_2") (pintype "passive"))
      (node (ref "C2") (pin "1") (pinfunction "1_1") (pintype "passive"))
      (node (ref "C20") (pin "1") (pinfunction "1_1") (pintype "passive"))
      (node (ref "C21") (pin "1") (pinfunction "1_1") (pintype "passive"))
      (node (ref "C23") (pin "2") (pinfunction "2_2") (pintype "passive"))
      (node (ref "C24") (pin "2") (pinfunction "2_2") (pintype "passive"))
      (node (ref "C25") (pin "2") (pinfunction "2_2") (pintype "passive"))
      (node (ref "C26") (pin "2") (pinfunction "2_2") (pintype "passive"))
      (node (ref "C27") (pin "2") (pinfunction "2_2") (pintype "passive"))
      (node (ref "C28") (pin "2") (pinfunction "2_2") (pintype "passive"))
      (node (ref "C29") (pin "2") (pinfunction "2_2") (pintype "passive"))
      (node (ref "C3") (pin "2") (pinfunction "2_2") (pintype "passive"))
      (node (ref "C4") (pin "2") (pinfunction "2_2") (pintype "passive"))
      (node (ref "C5") (pin "-") (pinfunction "-_-") (pintype "passive"))
      (node (ref "C6") (pin "-") (pinfunction "-_-") (pintype "passive"))
      (node (ref "C7") (pin "2") (pinfunction "2_2") (pintype "passive"))
      (node (ref "C8") (pin "1") (pinfunction "1_1") (pintype "passive"))
      (node (ref "C9") (pin "2") (pinfunction "2_2") (pintype "passive"))
      (node (ref "IC1") (pin "1") (pinfunction "ADJ_1") (pintype "input"))
      (node (ref "IC2") (pin "28") (pinfunction "UGND_28") (pintype "power_in"))
      (node (ref "IC2") (pin "3") (pinfunction "GND_3") (pintype "power_in"))
      (node (ref "IC2") (pin "EXP") (pinfunction "PAD_EXP") (pintype "power_in"))
      (node (ref "IC3") (pin "21") (pinfunction "AGND_21") (pintype "bidirectional"))
      (node (ref "IC3") (pin "3") (pinfunction "GND_3") (pintype "bidirectional"))
      (node (ref "IC3") (pin "5") (pinfunction "GND_5") (pintype "bidirectional"))
      (node (ref "IC4") (pin "4") (pinfunction "V-_4") (pintype "power_in"))
      (node (ref "IC5") (pin "14") (pinfunction "AGND_14") (pintype "passive"))
      (node (ref "IC5") (pin "16") (pinfunction "AGND_16") (pintype "passive"))
      (node (ref "IC5") (pin "19") (pinfunction "AGND_19") (pintype "passive"))
      (node (ref "IC5") (pin "29") (pinfunction "GND_29") (pintype "passive"))
      (node (ref "IC5") (pin "3") (pinfunction "AGND_3") (pintype "passive"))
      (node (ref "IC5") (pin "48") (pinfunction "AGND_48") (pintype "passive"))
      (node (ref "IC5") (pin "9") (pinfunction "AGND_9") (pintype "passive"))
      (node (ref "IC6") (pin "2") (pinfunction "GND_2") (pintype "power_in"))
      (node (ref "IC6") (pin "4") (pinfunction "A1_4") (pintype "input"))
      (node (ref "IC6") (pin "5") (pinfunction "A0_5") (pintype "input"))
      (node (ref "J1") (pin "7") (pinfunction "7_7") (pintype "passive"))
      (node (ref "J10") (pin "6") (pinfunction "6_6") (pintype "passive"))
      (node (ref "J11") (pin "6") (pinfunction "GND_6") (pintype "bidirectional"))
      (node (ref "J11") (pin "CD2") (pinfunction "CD2_CD2") (pintype "bidirectional"))
      (node (ref "J11") (pin "GND1") (pinfunction "SHIELD1_GND1") (pintype "bidirectional"))
      (node (ref "J11") (pin "GND2") (pinfunction "SHIELD2_GND2") (pintype "bidirectional"))
      (node (ref "J2") (pin "6") (pinfunction "6_6") (pintype "passive"))
      (node (ref "J2") (pin "7") (pinfunction "7_7") (pintype "passive"))
      (node (ref "J5") (pin "GND") (pinfunction "GND_GND") (pintype "bidirectional"))
      (node (ref "J5") (pin "GNDBREAK") (pinfunction "GNDBREAK_GNDBREAK") (pintype "bidirectional"))
      (node (ref "J6") (pin "A12B1") (pinfunction "GND_A12B1") (pintype "power_in"))
      (node (ref "J6") (pin "A1B12") (pinfunction "GND_A1B12") (pintype "power_in"))
      (node (ref "J6") (pin "FIX1") (pinfunction "GND_FIX1") (pintype "power_in"))
      (node (ref "J6") (pin "FIX2") (pinfunction "GND_FIX2") (pintype "power_in"))
      (node (ref "J6") (pin "FIX3") (pinfunction "GND_FIX3") (pintype "power_in"))
      (node (ref "J6") (pin "FIX4") (pinfunction "GND_FIX4") (pintype "power_in"))
      (node (ref "J8") (pin "1") (pinfunction "GND[1]_1") (pintype "passive"))
      (node (ref "J9") (pin "6") (pinfunction "6_6") (pintype "passive"))
      (node (ref "Q2") (pin "2") (pinfunction "S_2") (pintype "passive"))
      (node (ref "R10") (pin "2") (pinfunction "2_2") (pintype "passive"))
      (node (ref "R6") (pin "1") (pinfunction "1_1") (pintype "passive"))
      (node (ref "R7") (pin "1") (pinfunction "1_1") (pintype "passive"))
      (node (ref "R9") (pin "2") (pinfunction "2_2") (pintype "passive"))
      (node (ref "RN4") (pin "4") (pinfunction "1_4") (pintype "passive"))
      (node (ref "RN6") (pin "1") (pinfunction "1_1") (pintype "passive"))
      (node (ref "RN7") (pin "1") (pinfunction "1_1") (pintype "passive"))
      (node (ref "RN7") (pin "2") (pinfunction "1_2") (pintype "passive"))
      (node (ref "RN7") (pin "3") (pinfunction "1_3") (pintype "passive"))
      (node (ref "RN8") (pin "5") (pinfunction "2_5") (pintype "passive"))
      (node (ref "RN9") (pin "5") (pinfunction "2_5") (pintype "passive"))
      (node (ref "RN9") (pin "6") (pinfunction "2_6") (pintype "passive"))
      (node (ref "RN9") (pin "7") (pinfunction "2_7") (pintype "passive"))
      (node (ref "RN9") (pin "8") (pinfunction "2_8") (pintype "passive"))
      (node (ref "S1") (pin "1") (pinfunction "1_1") (pintype "passive"))
      (node (ref "S1") (pin "2") (pinfunction "2_2") (pintype "passive"))
      (node (ref "SJ2") (pin "1") (pinfunction "1_1") (pintype "passive"))
      (node (ref "U1") (pin "GND1") (pinfunction "GND1_GND1") (pintype "bidirectional"))
      (node (ref "U1") (pin "GND2") (pinfunction "GND2_GND2") (pintype "bidirectional"))
      (node (ref "VR1") (pin "1") (pinfunction "GND_1") (pintype "input"))
      (node (ref "VR2") (pin "1") (pinfunction "GND_1") (pintype "input"))
      (node (ref "XTL1") (pin "2") (pinfunction "GND_2") (pintype "bidirectional"))
      (node (ref "XTL1") (pin "4") (pinfunction "GND_4") (pintype "bidirectional"))
      (node (ref "XTL2") (pin "2") (pinfunction "GND_2") (pintype "bidirectional"))
      (node (ref "XTL2") (pin "4") (pinfunction "GND_4") (pintype "bidirectional"))
      (node (ref "XTL3") (pin "2") (pinfunction "GND_2") (pintype "bidirectional"))
      (node (ref "XTL3") (pin "4") (pinfunction "GND_4") (pintype "bidirectional"))
      (node (ref "Z1") (pin "2") (pinfunction "2_2") (pintype "passive"))
      (node (ref "Z2") (pin "2") (pinfunction "2_2") (pintype "passive"))
    )
    (net (code "32") (name "LINKLED") (class "Default")
      (node (ref "IC5") (pin "25") (pinfunction "~{LINK}_25") (pintype "passive"))
      (node (ref "RN2") (pin "4") (pinfunction "1_4") (pintype "passive"))
      (node (ref "RN2") (pin "7") (pinfunction "2_7") (pintype "passive"))
    )
    (net (code "33") (name "Net-(C19-Pad1)") (class "Default")
      (node (ref "C19") (pin "1") (pinfunction "1_1") (pintype "passive"))
      (node (ref "SJ1") (pin "2") (pinfunction "2_2") (pintype "passive"))
    )
    (net (code "34") (name "Net-(CD-Pad1)") (class "Default")
      (node (ref "CD") (pin "1") (pinfunction "1_1") (pintype "passive"))
      (node (ref "J11") (pin "CD1") (pinfunction "CD1_CD1") (pintype "bidirectional"))
    )
    (net (code "35") (name "Net-(D1-PadA)") (class "Default")
      (node (ref "D1") (pin "A") (pinfunction "A_A") (pintype "passive"))
      (node (ref "J5") (pin "PWR") (pinfunction "PWR_PWR") (pintype "bidirectional"))
    )
    (net (code "36") (name "Net-(F1-Pad1)") (class "Default")
      (node (ref "F1") (pin "1") (pinfunction "1_1") (pintype "passive"))
      (node (ref "J6") (pin "A4B9") (pinfunction "VBUS_A4B9") (pintype "power_in"))
      (node (ref "J6") (pin "A9B4") (pinfunction "VBUS_A9B4") (pintype "power_in"))
    )
    (net (code "37") (name "Net-(IC2-UCAP)") (class "Default")
      (node (ref "C11") (pin "1") (pinfunction "1_1") (pintype "passive"))
      (node (ref "IC2") (pin "27") (pinfunction "UCAP_27") (pintype "passive"))
    )
    (net (code "38") (name "Net-(IC2-XTAL1)") (class "Default")
      (node (ref "C8") (pin "2") (pinfunction "2_2") (pintype "passive"))
      (node (ref "IC2") (pin "1") (pinfunction "XTAL1_1") (pintype "bidirectional"))
      (node (ref "XTL1") (pin "3") (pinfunction "2_3") (pintype "passive"))
    )
    (net (code "39") (name "Net-(IC2-XTAL2)") (class "Default")
      (node (ref "C2") (pin "2") (pinfunction "2_2") (pintype "passive"))
      (node (ref "IC2") (pin "2") (pinfunction "XTAL2_2") (pintype "bidirectional"))
      (node (ref "XTL1") (pin "1") (pinfunction "1_1") (pintype "passive"))
    )
    (net (code "40") (name "Net-(IC3-ADC6)") (class "Default")
      (node (ref "A6") (pin "1") (pinfunction "1_1") (pintype "passive"))
      (node (ref "IC3") (pin "19") (pinfunction "ADC6_19") (pintype "bidirectional"))
    )
    (net (code "41") (name "Net-(IC3-ADC7)") (class "Default")
      (node (ref "A7") (pin "1") (pinfunction "1_1") (pintype "passive"))
      (node (ref "IC3") (pin "22") (pinfunction "ADC7_22") (pintype "bidirectional"))
    )
    (net (code "42") (name "Net-(IC3-PB6(XTAL1{slash}TOSC1))") (class "Default")
      (node (ref "C20") (pin "2") (pinfunction "2_2") (pintype "passive"))
      (node (ref "IC3") (pin "7") (pinfunction "PB6(XTAL1/TOSC1)_7") (pintype "bidirectional"))
      (node (ref "XTL2") (pin "1") (pinfunction "1_1") (pintype "passive"))
    )
    (net (code "43") (name "Net-(IC3-PB7(XTAL2{slash}TOSC2))") (class "Default")
      (node (ref "C21") (pin "2") (pinfunction "2_2") (pintype "passive"))
      (node (ref "IC3") (pin "8") (pinfunction "PB7(XTAL2/TOSC2)_8") (pintype "bidirectional"))
      (node (ref "XTL2") (pin "3") (pinfunction "2_3") (pintype "passive"))
    )
    (net (code "44") (name "Net-(IC4A-+IN)") (class "Default")
      (node (ref "IC4") (pin "3") (pinfunction "+IN_3") (pintype "input"))
      (node (ref "RN4") (pin "5") (pinfunction "2_5") (pintype "passive"))
      (node (ref "RN4") (pin "6") (pinfunction "2_6") (pintype "passive"))
    )
    (net (code "45") (name "Net-(IC4A-OUT)") (class "Default")
      (node (ref "IC4") (pin "1") (pinfunction "OUT_1") (pintype "output"))
      (node (ref "IC4") (pin "5") (pinfunction "+IN_5") (pintype "input"))
    )
    (net (code "46") (name "Net-(IC4B--IN)") (class "Default")
      (node (ref "IC4") (pin "6") (pinfunction "-IN_6") (pintype "input"))
      (node (ref "IC4") (pin "7") (pinfunction "OUT_7") (pintype "output"))
      (node (ref "Q1") (pin "1") (pinfunction "G_1") (pintype "passive"))
    )
    (net (code "47") (name "Net-(IC5-EXRES1)") (class "Default")
      (node (ref "IC5") (pin "10") (pinfunction "EXRES1_10") (pintype "passive"))
      (node (ref "R10") (pin "1") (pinfunction "1_1") (pintype "passive"))
    )
    (net (code "48") (name "Net-(IC5-MOD0)") (class "Default")
      (node (ref "IC5") (pin "45") (pinfunction "MOD0_45") (pintype "passive"))
      (node (ref "RN8") (pin "1") (pinfunction "1_1") (pintype "passive"))
    )
    (net (code "49") (name "Net-(IC5-MOD1)") (class "Default")
      (node (ref "IC5") (pin "44") (pinfunction "MOD1_44") (pintype "passive"))
      (node (ref "RN8") (pin "2") (pinfunction "1_2") (pintype "passive"))
    )
    (net (code "50") (name "Net-(IC5-MOD2)") (class "Default")
      (node (ref "IC5") (pin "43") (pinfunction "MOD2_43") (pintype "passive"))
      (node (ref "RN8") (pin "3") (pinfunction "1_3") (pintype "passive"))
    )
    (net (code "51") (name "Net-(IC5-RSVD)") (class "Default")
      (node (ref "IC5") (pin "23") (pinfunction "RSVD_23") (pintype "passive"))
      (node (ref "R9") (pin "1") (pinfunction "1_1") (pintype "passive"))
    )
    (net (code "52") (name "Net-(IC5-RSVD1)") (class "Default")
      (node (ref "IC5") (pin "38") (pinfunction "RSVD1_38") (pintype "passive"))
      (node (ref "RN9") (pin "4") (pinfunction "1_4") (pintype "passive"))
    )
    (net (code "53") (name "Net-(IC5-RSVD2)") (class "Default")
      (node (ref "IC5") (pin "39") (pinfunction "RSVD2_39") (pintype "passive"))
      (node (ref "RN9") (pin "3") (pinfunction "1_3") (pintype "passive"))
    )
    (net (code "54") (name "Net-(IC5-RSVD3)") (class "Default")
      (node (ref "IC5") (pin "40") (pinfunction "RSVD3_40") (pintype "passive"))
      (node (ref "RN9") (pin "2") (pinfunction "1_2") (pintype "passive"))
    )
    (net (code "55") (name "Net-(IC5-RSVD4)") (class "Default")
      (node (ref "IC5") (pin "41") (pinfunction "RSVD4_41") (pintype "passive"))
      (node (ref "RN9") (pin "1") (pinfunction "1_1") (pintype "passive"))
    )
    (net (code "56") (name "Net-(IC5-RSVD5)") (class "Default")
      (node (ref "IC5") (pin "42") (pinfunction "RSVD5_42") (pintype "passive"))
      (node (ref "RN8") (pin "4") (pinfunction "1_4") (pintype "passive"))
    )
    (net (code "57") (name "Net-(IC5-TOCAP)") (class "Default")
      (node (ref "C16") (pin "1") (pinfunction "1_1") (pintype "passive"))
      (node (ref "IC5") (pin "20") (pinfunction "TOCAP_20") (pintype "passive"))
    )
    (net (code "58") (name "Net-(IC5-XI{slash}CLKIN)") (class "Default")
      (node (ref "C3") (pin "1") (pinfunction "1_1") (pintype "passive"))
      (node (ref "IC5") (pin "30") (pinfunction "XI/CLKIN_30") (pintype "passive"))
      (node (ref "R11") (pin "2") (pinfunction "2_2") (pintype "passive"))
      (node (ref "XTL3") (pin "1") (pinfunction "1_1") (pintype "passive"))
    )
    (net (code "59") (name "Net-(IC5-XO)") (class "Default")
      (node (ref "C4") (pin "1") (pinfunction "1_1") (pintype "passive"))
      (node (ref "IC5") (pin "31") (pinfunction "XO_31") (pintype "passive"))
      (node (ref "R11") (pin "1") (pinfunction "1_1") (pintype "passive"))
      (node (ref "XTL3") (pin "3") (pinfunction "2_3") (pintype "passive"))
    )
    (net (code "60") (name "Net-(IC5-~{INT})") (class "Default")
      (node (ref "IC5") (pin "36") (pinfunction "~{INT}_36") (pintype "passive"))
      (node (ref "J7") (pin "1") (pinfunction "1_1") (pintype "passive"))
      (node (ref "R8") (pin "1") (pinfunction "1_1") (pintype "passive"))
    )
    (net (code "61") (name "Net-(IC6-SCL)") (class "Default")
      (node (ref "IC6") (pin "1") (pinfunction "SCL_1") (pintype "bidirectional"))
      (node (ref "R5") (pin "2") (pinfunction "2_2") (pintype "passive"))
      (node (ref "SJ4") (pin "2") (pinfunction "2_2") (pintype "passive"))
    )
    (net (code "62") (name "Net-(IC6-SDA)") (class "Default")
      (node (ref "IC6") (pin "3") (pinfunction "SDA_3") (pintype "bidirectional"))
      (node (ref "R4") (pin "2") (pinfunction "2_2") (pintype "passive"))
      (node (ref "SJ3") (pin "2") (pinfunction "2_2") (pintype "passive"))
    )
    (net (code "63") (name "Net-(J6-CC1)") (class "Default")
      (node (ref "J6") (pin "A5") (pinfunction "CC1_A5") (pintype "bidirectional"))
      (node (ref "R7") (pin "2") (pinfunction "2_2") (pintype "passive"))
    )
    (net (code "64") (name "Net-(J6-CC2)") (class "Default")
      (node (ref "J6") (pin "B5") (pinfunction "CC2_B5") (pintype "bidirectional"))
      (node (ref "R6") (pin "2") (pinfunction "2_2") (pintype "passive"))
    )
    (net (code "65") (name "Net-(J6-D+-PadA6)") (class "Default")
      (node (ref "J6") (pin "A6") (pinfunction "D+_A6") (pintype "bidirectional"))
      (node (ref "J6") (pin "B6") (pinfunction "D+_B6") (pintype "bidirectional"))
      (node (ref "R2") (pin "2") (pinfunction "2_2") (pintype "passive"))
      (node (ref "Z1") (pin "1") (pinfunction "1_1") (pintype "passive"))
    )
    (net (code "66") (name "Net-(J6-D--PadA7)") (class "Default")
      (node (ref "J6") (pin "A7") (pinfunction "D-_A7") (pintype "bidirectional"))
      (node (ref "J6") (pin "B7") (pinfunction "D-_B7") (pintype "bidirectional"))
      (node (ref "R1") (pin "2") (pinfunction "2_2") (pintype "passive"))
      (node (ref "Z2") (pin "1") (pinfunction "1_1") (pintype "passive"))
    )
    (net (code "67") (name "Net-(J8-V+[3])") (class "Default")
      (node (ref "J8") (pin "3") (pinfunction "V+[3]_3") (pintype "passive"))
      (node (ref "U1") (pin "P$9") (pinfunction "V+_P$9") (pintype "bidirectional"))
    )
    (net (code "68") (name "Net-(J8-V-[2])") (class "Default")
      (node (ref "J8") (pin "2") (pinfunction "V-[2]_2") (pintype "passive"))
      (node (ref "U1") (pin "P$10") (pinfunction "V-_P$10") (pintype "bidirectional"))
    )
    (net (code "69") (name "Net-(J8-VIN[4])") (class "Default")
      (node (ref "D2") (pin "A") (pinfunction "A_A") (pintype "passive"))
      (node (ref "J8") (pin "4") (pinfunction "VIN[4]_4") (pintype "passive"))
    )
    (net (code "70") (name "Net-(J11-CS)") (class "Default")
      (node (ref "J11") (pin "2") (pinfunction "CS_2") (pintype "bidirectional"))
      (node (ref "RN6") (pin "4") (pinfunction "1_4") (pintype "passive"))
      (node (ref "RN7") (pin "8") (pinfunction "2_8") (pintype "passive"))
    )
    (net (code "71") (name "Net-(J11-DI)") (class "Default")
      (node (ref "J11") (pin "3") (pinfunction "DI_3") (pintype "bidirectional"))
      (node (ref "RN6") (pin "3") (pinfunction "1_3") (pintype "passive"))
      (node (ref "RN7") (pin "6") (pinfunction "2_6") (pintype "passive"))
    )
    (net (code "72") (name "Net-(J11-SCK)") (class "Default")
      (node (ref "J11") (pin "5") (pinfunction "SCK_5") (pintype "bidirectional"))
      (node (ref "RN6") (pin "2") (pinfunction "1_2") (pintype "passive"))
      (node (ref "RN7") (pin "7") (pinfunction "2_7") (pintype "passive"))
    )
    (net (code "73") (name "Net-(LED3-PadC)") (class "Default")
      (node (ref "LED3") (pin "C") (pinfunction "C_C") (pintype "passive"))
      (node (ref "RN3") (pin "1") (pinfunction "1_1") (pintype "passive"))
    )
    (net (code "74") (name "Net-(LED8-PadC)") (class "Default")
      (node (ref "LED8") (pin "C") (pinfunction "C_C") (pintype "passive"))
      (node (ref "R3") (pin "2") (pinfunction "2_2") (pintype "passive"))
    )
    (net (code "75") (name "Net-(Q2-D)") (class "Default")
      (node (ref "Q2") (pin "3") (pinfunction "D_3") (pintype "passive"))
      (node (ref "R3") (pin "1") (pinfunction "1_1") (pintype "passive"))
    )
    (net (code "76") (name "Net-(RN1B-2)") (class "Default")
      (node (ref "LED2") (pin "C") (pinfunction "C_C") (pintype "passive"))
      (node (ref "RN1") (pin "7") (pinfunction "2_7") (pintype "passive"))
    )
    (net (code "77") (name "Net-(RN1D-2)") (class "Default")
      (node (ref "LED5") (pin "C") (pinfunction "C_C") (pintype "passive"))
      (node (ref "RN1") (pin "5") (pinfunction "2_5") (pintype "passive"))
    )
    (net (code "78") (name "Net-(RN2B-1)") (class "Default")
      (node (ref "RN2") (pin "2") (pinfunction "1_2") (pintype "passive"))
      (node (ref "U1") (pin "P$12") (pinfunction "Y-_P$12") (pintype "bidirectional"))
    )
    (net (code "79") (name "Net-(RN2C-2)") (class "Default")
      (node (ref "LED6") (pin "C") (pinfunction "C_C") (pintype "passive"))
      (node (ref "RN2") (pin "6") (pinfunction "2_6") (pintype "passive"))
    )
    (net (code "80") (name "Net-(RN2D-2)") (class "Default")
      (node (ref "LED7") (pin "C") (pinfunction "C_C") (pintype "passive"))
      (node (ref "RN2") (pin "5") (pinfunction "2_5") (pintype "passive"))
    )
    (net (code "81") (name "Net-(RN3B-1)") (class "Default")
      (node (ref "LED4") (pin "C") (pinfunction "C_C") (pintype "passive"))
      (node (ref "RN3") (pin "2") (pinfunction "1_2") (pintype "passive"))
    )
    (net (code "82") (name "Net-(RN5A-2)") (class "Default")
      (node (ref "C23") (pin "1") (pinfunction "1_1") (pintype "passive"))
      (node (ref "RN5") (pin "7") (pinfunction "2_7") (pintype "passive"))
      (node (ref "RN5") (pin "8") (pinfunction "2_8") (pintype "passive"))
      (node (ref "U1") (pin "P$3") (pinfunction "RXCT_P$3") (pintype "bidirectional"))
    )
    (net (code "83") (name "Net-(RN6A-2)") (class "Default")
      (node (ref "LED1") (pin "C") (pinfunction "C_C") (pintype "passive"))
      (node (ref "RN6") (pin "8") (pinfunction "2_8") (pintype "passive"))
    )
    (net (code "84") (name "Net-(RN6D-2)") (class "Default")
      (node (ref "RN6") (pin "5") (pinfunction "2_5") (pintype "passive"))
      (node (ref "U$2") (pin "1") (pinfunction "1_1") (pintype "passive"))
    )
    (net (code "85") (name "Net-(U1-G-)") (class "Default")
      (node (ref "RN2") (pin "1") (pinfunction "1_1") (pintype "passive"))
      (node (ref "U1") (pin "P$14") (pinfunction "G-_P$14") (pintype "bidirectional"))
    )
    (net (code "86") (name "Net-(U1-TXCT)") (class "Default")
      (node (ref "C24") (pin "1") (pinfunction "1_1") (pintype "passive"))
      (node (ref "R12") (pin "2") (pinfunction "2_2") (pintype "passive"))
      (node (ref "U1") (pin "P$4") (pinfunction "TXCT_P$4") (pintype "bidirectional"))
    )
    (net (code "87") (name "RD+") (class "Default")
      (node (ref "IC2") (pin "29") (pinfunction "D+_29") (pintype "bidirectional"))
      (node (ref "R2") (pin "1") (pinfunction "1_1") (pintype "passive"))
    )
    (net (code "88") (name "RD-") (class "Default")
      (node (ref "IC2") (pin "30") (pinfunction "D-_30") (pintype "bidirectional"))
      (node (ref "R1") (pin "1") (pinfunction "1_1") (pintype "passive"))
    )
    (net (code "89") (name "RESET") (class "Default")
      (node (ref "C19") (pin "2") (pinfunction "2_2") (pintype "passive"))
      (node (ref "IC3") (pin "29") (pinfunction "PC6(/RESET)_29") (pintype "bidirectional"))
      (node (ref "IC5") (pin "37") (pinfunction "~{RESET}_37") (pintype "passive"))
      (node (ref "J2") (pin "3") (pinfunction "3_3") (pintype "passive"))
      (node (ref "J9") (pin "5") (pinfunction "5_5") (pintype "passive"))
      (node (ref "RN4") (pin "2") (pinfunction "1_2") (pintype "passive"))
      (node (ref "S1") (pin "3") (pinfunction "3_3") (pintype "passive"))
      (node (ref "S1") (pin "4") (pinfunction "4_4") (pintype "passive"))
    )
    (net (code "90") (name "RESET2") (class "Default")
      (node (ref "IC2") (pin "24") (pinfunction "RESET_24") (pintype "input"))
      (node (ref "J10") (pin "5") (pinfunction "5_5") (pintype "passive"))
      (node (ref "RN4") (pin "1") (pinfunction "1_1") (pintype "passive"))
    )
    (net (code "91") (name "RXIN") (class "Default")
      (node (ref "IC5") (pin "5") (pinfunction "RXIN_5") (pintype "passive"))
      (node (ref "RN5") (pin "2") (pinfunction "1_2") (pintype "passive"))
      (node (ref "U1") (pin "P$2") (pinfunction "RX-_P$2") (pintype "bidirectional"))
    )
    (net (code "92") (name "RXIP") (class "Default")
      (node (ref "IC5") (pin "6") (pinfunction "RXIP_6") (pintype "passive"))
      (node (ref "RN5") (pin "1") (pinfunction "1_1") (pintype "passive"))
      (node (ref "U1") (pin "P$1") (pinfunction "RX+_P$1") (pintype "bidirectional"))
    )
    (net (code "93") (name "RXLED") (class "Default")
      (node (ref "IC2") (pin "10") (pinfunction "PD4_10") (pintype "bidirectional"))
      (node (ref "RN3") (pin "7") (pinfunction "2_7") (pintype "passive"))
    )
    (net (code "94") (name "SCK2") (class "Default")
      (node (ref "IC2") (pin "15") (pinfunction "(SCLK)PB1_15") (pintype "bidirectional"))
      (node (ref "J10") (pin "3") (pinfunction "3_3") (pintype "passive"))
    )
    (net (code "95") (name "SPDLED") (class "Default")
      (node (ref "IC5") (pin "24") (pinfunction "~{SPD}_24") (pintype "passive"))
      (node (ref "RN2") (pin "3") (pinfunction "1_3") (pintype "passive"))
    )
    (net (code "96") (name "TXLED") (class "Default")
      (node (ref "IC2") (pin "11") (pinfunction "(XCK)PD5_11") (pintype "bidirectional"))
      (node (ref "RN3") (pin "8") (pinfunction "2_8") (pintype "passive"))
    )
    (net (code "97") (name "TXON") (class "Default")
      (node (ref "IC5") (pin "1") (pinfunction "TXON_1") (pintype "passive"))
      (node (ref "RN5") (pin "4") (pinfunction "1_4") (pintype "passive"))
      (node (ref "U1") (pin "P$6") (pinfunction "TX-_P$6") (pintype "bidirectional"))
    )
    (net (code "98") (name "TXOP") (class "Default")
      (node (ref "IC5") (pin "2") (pinfunction "TXOP_2") (pintype "passive"))
      (node (ref "RN5") (pin "3") (pinfunction "1_3") (pintype "passive"))
      (node (ref "U1") (pin "P$5") (pinfunction "TX+_P$5") (pintype "bidirectional"))
    )
    (net (code "99") (name "USBRXD") (class "Default")
      (node (ref "IC2") (pin "9") (pinfunction "(TXD1)PD3_9") (pintype "bidirectional"))
      (node (ref "RN3") (pin "5") (pinfunction "2_5") (pintype "passive"))
    )
    (net (code "100") (name "USBTXD") (class "Default")
      (node (ref "IC2") (pin "8") (pinfunction "(RXD1)PD2_8") (pintype "bidirectional"))
      (node (ref "RN3") (pin "6") (pinfunction "2_6") (pintype "passive"))
    )
    (net (code "101") (name "USBVCC") (class "Default")
      (node (ref "F1") (pin "2") (pinfunction "2_2") (pintype "passive"))
      (node (ref "IC2") (pin "31") (pinfunction "UVCC_31") (pintype "power_in"))
      (node (ref "Q1") (pin "3") (pinfunction "D_3") (pintype "passive"))
    )
    (net (code "102") (name "VIN") (class "Default")
      (node (ref "C5") (pin "+") (pinfunction "+_+") (pintype "passive"))
      (node (ref "D1") (pin "C") (pinfunction "C_C") (pintype "passive"))
      (node (ref "D2") (pin "C") (pinfunction "C_C") (pintype "passive"))
      (node (ref "IC1") (pin "3") (pinfunction "VI_3") (pintype "input"))
      (node (ref "J2") (pin "8") (pinfunction "8_8") (pintype "passive"))
      (node (ref "RN4") (pin "3") (pinfunction "1_3") (pintype "passive"))
    )
    (net (code "103") (name "unconnected-(IC2-(RTS)PD6-Pad12)") (class "Default")
      (node (ref "IC2") (pin "12") (pinfunction "(RTS)PD6_12") (pintype "bidirectional"))
    )
    (net (code "104") (name "unconnected-(IC2-(SS)PB0-Pad14)") (class "Default")
      (node (ref "IC2") (pin "14") (pinfunction "(SS)PB0_14") (pintype "bidirectional"))
    )
    (net (code "105") (name "unconnected-(IC2-PB4-Pad18)") (class "Default")
      (node (ref "IC2") (pin "18") (pinfunction "PB4_18") (pintype "bidirectional"))
    )
    (net (code "106") (name "unconnected-(IC2-PB5-Pad19)") (class "Default")
      (node (ref "IC2") (pin "19") (pinfunction "PB5_19") (pintype "bidirectional"))
    )
    (net (code "107") (name "unconnected-(IC2-PB6-Pad20)") (class "Default")
      (node (ref "IC2") (pin "20") (pinfunction "PB6_20") (pintype "bidirectional"))
    )
    (net (code "108") (name "unconnected-(IC2-PB7-Pad21)") (class "Default")
      (node (ref "IC2") (pin "21") (pinfunction "PB7_21") (pintype "bidirectional"))
    )
    (net (code "109") (name "unconnected-(IC2-PC2-Pad5)") (class "Default")
      (node (ref "IC2") (pin "5") (pinfunction "PC2_5") (pintype "bidirectional"))
    )
    (net (code "110") (name "unconnected-(IC2-PC4-Pad26)") (class "Default")
      (node (ref "IC2") (pin "26") (pinfunction "PC4_26") (pintype "bidirectional"))
    )
    (net (code "111") (name "unconnected-(IC2-PC5-Pad25)") (class "Default")
      (node (ref "IC2") (pin "25") (pinfunction "PC5_25") (pintype "bidirectional"))
    )
    (net (code "112") (name "unconnected-(IC2-PC6-Pad23)") (class "Default")
      (node (ref "IC2") (pin "23") (pinfunction "PC6_23") (pintype "bidirectional"))
    )
    (net (code "113") (name "unconnected-(IC2-PC7-Pad22)") (class "Default")
      (node (ref "IC2") (pin "22") (pinfunction "PC7_22") (pintype "bidirectional"))
    )
    (net (code "114") (name "unconnected-(IC2-PD0-Pad6)") (class "Default")
      (node (ref "IC2") (pin "6") (pinfunction "PD0_6") (pintype "bidirectional"))
    )
    (net (code "115") (name "unconnected-(IC2-PD1-Pad7)") (class "Default")
      (node (ref "IC2") (pin "7") (pinfunction "PD1_7") (pintype "bidirectional"))
    )
    (net (code "116") (name "unconnected-(IC5-DNC-Pad7)") (class "Default")
      (node (ref "IC5") (pin "7") (pinfunction "DNC_7") (pintype "passive"))
    )
    (net (code "117") (name "unconnected-(IC5-NC-Pad12)") (class "Default")
      (node (ref "IC5") (pin "12") (pinfunction "NC_12") (pintype "passive"))
    )
    (net (code "118") (name "unconnected-(IC5-NC-Pad13)") (class "Default")
      (node (ref "IC5") (pin "13") (pinfunction "NC_13") (pintype "passive"))
    )
    (net (code "119") (name "unconnected-(IC5-NC-Pad46)") (class "Default")
      (node (ref "IC5") (pin "46") (pinfunction "NC_46") (pintype "passive"))
    )
    (net (code "120") (name "unconnected-(IC5-NC-Pad47)") (class "Default")
      (node (ref "IC5") (pin "47") (pinfunction "NC_47") (pintype "passive"))
    )
    (net (code "121") (name "unconnected-(IC5-VBG-Pad18)") (class "Default")
      (node (ref "IC5") (pin "18") (pinfunction "VBG_18") (pintype "passive"))
    )
    (net (code "122") (name "unconnected-(J2-Pad1)") (class "Default")
      (node (ref "J2") (pin "1") (pinfunction "1_1") (pintype "passive"))
    )
    (net (code "123") (name "unconnected-(J6-SBU1-PadA8)") (class "Default")
      (node (ref "J6") (pin "A8") (pinfunction "SBU1_A8") (pintype "bidirectional"))
    )
    (net (code "124") (name "unconnected-(J6-SBU2-PadB8)") (class "Default")
      (node (ref "J6") (pin "B8") (pinfunction "SBU2_B8") (pintype "bidirectional"))
    )
    (net (code "125") (name "unconnected-(J8-PadMNT1)") (class "Default")
      (node (ref "J8") (pin "MNT1") (pinfunction "MNT1_MNT1") (pintype "passive"))
    )
    (net (code "126") (name "unconnected-(J8-PadMNT2)") (class "Default")
      (node (ref "J8") (pin "MNT2") (pinfunction "MNT2_MNT2") (pintype "passive"))
    )
    (net (code "127") (name "unconnected-(J11-NC-Pad1)") (class "Default")
      (node (ref "J11") (pin "1") (pinfunction "NC_1") (pintype "bidirectional"))
    )
    (net (code "128") (name "unconnected-(J11-RSV-Pad8)") (class "Default")
      (node (ref "J11") (pin "8") (pinfunction "RSV_8") (pintype "bidirectional"))
    )
    (net (code "129") (name "unconnected-(RN1-Pad1)") (class "Default")
      (node (ref "RN1") (pin "1") (pinfunction "1_1") (pintype "passive"))
    )
    (net (code "130") (name "unconnected-(RN1A-2-Pad8)") (class "Default")
      (node (ref "RN1") (pin "8") (pinfunction "2_8") (pintype "passive"))
    )
    (net (code "131") (name "unconnected-(RN1C-1-Pad3)") (class "Default")
      (node (ref "RN1") (pin "3") (pinfunction "1_3") (pintype "passive"))
    )
    (net (code "132") (name "unconnected-(RN1C-2-Pad6)") (class "Default")
      (node (ref "RN1") (pin "6") (pinfunction "2_6") (pintype "passive"))
    )
    (net (code "133") (name "unconnected-(RN7D-1-Pad4)") (class "Default")
      (node (ref "RN7") (pin "4") (pinfunction "1_4") (pintype "passive"))
    )
    (net (code "134") (name "unconnected-(RN7D-2-Pad5)") (class "Default")
      (node (ref "RN7") (pin "5") (pinfunction "2_5") (pintype "passive"))
    )
  )
)
